# Dogfish3D_-_Driver_Channel.net
KiCad netlist of a schematic drawn in Altium Designer
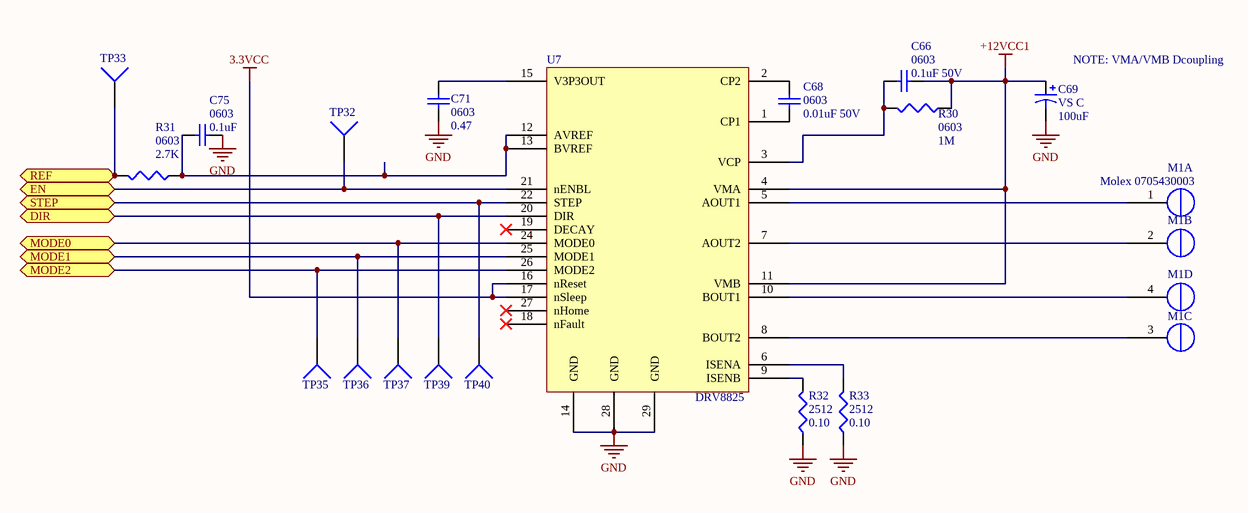
[diagram p0: Dogfish3D - Driver Channel.SchDoc]

(export (version "E")
  (design (tool "Eeschema 10.0.6"))
  (components
    (comp (ref "C66")
      (value "0603")
      (footprint "1608[0603]")
      (description "Capacitor (Semiconductor SIM Model)")
      (fields (field (name "ALTIUM_VALUE") "0.1uF 50V") (field (name "PUBLISHER") "Altium Limited"))
      (libsource (lib "Miscellaneous Devices") (part "Cap Semi"))
    )
    (comp (ref "C68")
      (value "0603")
      (footprint "1608[0603]")
      (description "Capacitor (Semiconductor SIM Model)")
      (fields (field (name "ALTIUM_VALUE") "0.01uF 50V") (field (name "PUBLISHER") "Altium Limited"))
      (libsource (lib "Miscellaneous Devices") (part "Cap Semi"))
    )
    (comp (ref "C69")
      (value "VS C")
      (footprint "Panasonic VS C")
      (description "Polarized Capacitor (Radial)")
      (fields (field (name "ALTIUM_VALUE") "100uF") (field (name "PUBLISHER") "Altium Limited"))
      (libsource (lib "Miscellaneous Devices") (part "Cap Pol1"))
    )
    (comp (ref "C71")
      (value "0603")
      (footprint "1608[0603]")
      (description "Capacitor (Semiconductor SIM Model)")
      (fields (field (name "ALTIUM_VALUE") "0.47") (field (name "PUBLISHER") "Altium Limited"))
      (libsource (lib "Miscellaneous Devices") (part "Cap Semi"))
    )
    (comp (ref "C75")
      (value "0603")
      (footprint "1608[0603]")
      (description "Capacitor (Semiconductor SIM Model)")
      (fields (field (name "ALTIUM_VALUE") "0.1uF") (field (name "PUBLISHER") "Altium Limited"))
      (libsource (lib "Miscellaneous Devices") (part "Cap Semi"))
    )
    (comp (ref "M1")
      (value "Molex 0705430003")
      (footprint "4POL254")
      (description "Molex 4 Pin Clip Connector")
      (libsource (lib "ZMBo Schematic Library") (part "Molex 0705430003 Alt"))
    )
    (comp (ref "R30")
      (value "0603")
      (footprint "J1-0603")
      (description "Resistor")
      (fields (field (name "ALTIUM_VALUE") "1M") (field (name "PUBLISHER") "Altium Limited"))
      (libsource (lib "Miscellaneous Devices") (part "Res3"))
    )
    (comp (ref "R31")
      (value "0603")
      (footprint "J1-0603")
      (description "Resistor")
      (fields (field (name "ALTIUM_VALUE") "2.7K") (field (name "PUBLISHER") "Altium Limited"))
      (libsource (lib "Miscellaneous Devices") (part "Res3"))
    )
    (comp (ref "R32")
      (value "2512")
      (footprint "Resistor2512")
      (description "Resistor")
      (fields (field (name "ALTIUM_VALUE") "0.10") (field (name "PUBLISHER") "Altium Limited"))
      (libsource (lib "Miscellaneous Devices") (part "Res3"))
    )
    (comp (ref "R33")
      (value "2512")
      (footprint "Resistor2512")
      (description "Resistor")
      (fields (field (name "ALTIUM_VALUE") "0.10") (field (name "PUBLISHER") "Altium Limited"))
      (libsource (lib "Miscellaneous Devices") (part "Res3"))
    )
    (comp (ref "TP32")
      (value "TP4")
      (footprint "TP-2")
      (description "Socket")
      (fields (field (name "PUBLISHER") "Altium Limited"))
      (libsource (lib "ZMBo Schematic Library") (part "Socket"))
    )
    (comp (ref "TP33")
      (value "TP4")
      (footprint "TP-2")
      (description "Socket")
      (fields (field (name "PUBLISHER") "Altium Limited"))
      (libsource (lib "ZMBo Schematic Library") (part "Socket"))
    )
    (comp (ref "TP35")
      (value "TP4")
      (footprint "TP-2")
      (description "Socket")
      (fields (field (name "PUBLISHER") "Altium Limited"))
      (libsource (lib "ZMBo Schematic Library") (part "Socket"))
    )
    (comp (ref "TP36")
      (value "TP4")
      (footprint "TP-2")
      (description "Socket")
      (fields (field (name "PUBLISHER") "Altium Limited"))
      (libsource (lib "ZMBo Schematic Library") (part "Socket"))
    )
    (comp (ref "TP37")
      (value "TP4")
      (footprint "TP-2")
      (description "Socket")
      (fields (field (name "PUBLISHER") "Altium Limited"))
      (libsource (lib "ZMBo Schematic Library") (part "Socket"))
    )
    (comp (ref "TP39")
      (value "TP4")
      (footprint "TP-2")
      (description "Socket")
      (fields (field (name "PUBLISHER") "Altium Limited"))
      (libsource (lib "ZMBo Schematic Library") (part "Socket"))
    )
    (comp (ref "TP40")
      (value "TP4")
      (footprint "TP-2")
      (description "Socket")
      (fields (field (name "PUBLISHER") "Altium Limited"))
      (libsource (lib "ZMBo Schematic Library") (part "Socket"))
    )
    (comp (ref "U7")
      (value "DRV8825")
      (footprint "DRV8825")
      (description "DRV8825 Ti Stepper Driver")
      (libsource (lib "ZMBo Schematic Library") (part "DRV8825"))
    )
  )
  (nets
    (net (code "1") (name "+12VCC1") (class "Default")
      (node (ref "C66") (pin "1") (pinfunction "1_1") (pintype "passive"))
      (node (ref "C69") (pin "1") (pinfunction "1_1") (pintype "passive"))
      (node (ref "R30") (pin "1") (pinfunction "1_1") (pintype "passive"))
      (node (ref "U7") (pin "11") (pinfunction "VMB_11") (pintype "passive"))
      (node (ref "U7") (pin "4") (pinfunction "VMA_4") (pintype "passive"))
    )
    (net (code "2") (name "/DIR") (class "Default")
      (node (ref "TP39") (pin "1") (pinfunction "1_1") (pintype "passive"))
      (node (ref "U7") (pin "20") (pinfunction "DIR_20") (pintype "passive"))
    )
    (net (code "3") (name "/EN") (class "Default")
      (node (ref "TP32") (pin "1") (pinfunction "1_1") (pintype "passive"))
      (node (ref "U7") (pin "21") (pinfunction "nENBL_21") (pintype "passive"))
    )
    (net (code "4") (name "/MODE0") (class "Default")
      (node (ref "TP37") (pin "1") (pinfunction "1_1") (pintype "passive"))
      (node (ref "U7") (pin "24") (pinfunction "MODE0_24") (pintype "passive"))
    )
    (net (code "5") (name "/MODE1") (class "Default")
      (node (ref "TP36") (pin "1") (pinfunction "1_1") (pintype "passive"))
      (node (ref "U7") (pin "25") (pinfunction "MODE1_25") (pintype "passive"))
    )
    (net (code "6") (name "/MODE2") (class "Default")
      (node (ref "TP35") (pin "1") (pinfunction "1_1") (pintype "passive"))
      (node (ref "U7") (pin "26") (pinfunction "MODE2_26") (pintype "passive"))
    )
    (net (code "7") (name "/REF") (class "Default")
      (node (ref "R31") (pin "2") (pinfunction "2_2") (pintype "passive"))
      (node (ref "TP33") (pin "1") (pinfunction "1_1") (pintype "passive"))
    )
    (net (code "8") (name "/STEP") (class "Default")
      (node (ref "TP40") (pin "1") (pinfunction "1_1") (pintype "passive"))
      (node (ref "U7") (pin "22") (pinfunction "STEP_22") (pintype "passive"))
    )
    (net (code "9") (name "3.3VCC") (class "Default")
      (node (ref "U7") (pin "16") (pinfunction "nReset_16") (pintype "passive"))
      (node (ref "U7") (pin "17") (pinfunction "nSleep_17") (pintype "passive"))
    )
    (net (code "10") (name "GND") (class "Default")
      (node (ref "C69") (pin "2") (pinfunction "2_2") (pintype "passive"))
      (node (ref "C71") (pin "1") (pinfunction "1_1") (pintype "passive"))
      (node (ref "C75") (pin "1") (pinfunction "1_1") (pintype "passive"))
      (node (ref "R32") (pin "1") (pinfunction "1_1") (pintype "passive"))
      (node (ref "R33") (pin "1") (pinfunction "1_1") (pintype "passive"))
      (node (ref "U7") (pin "14") (pinfunction "GND_14") (pintype "passive"))
      (node (ref "U7") (pin "28") (pinfunction "GND_28") (pintype "passive"))
      (node (ref "U7") (pin "29") (pinfunction "GND_29") (pintype "passive"))
    )
    (net (code "11") (name "Net-(M1A-OUT2B)") (class "Default")
      (node (ref "M1") (pin "1") (pinfunction "OUT2B_1") (pintype "passive"))
      (node (ref "U7") (pin "5") (pinfunction "AOUT1_5") (pintype "passive"))
    )
    (net (code "12") (name "Net-(M1B-OUT2A)") (class "Default")
      (node (ref "M1") (pin "2") (pinfunction "OUT2A_2") (pintype "passive"))
      (node (ref "U7") (pin "7") (pinfunction "AOUT2_7") (pintype "passive"))
    )
    (net (code "13") (name "Net-(M1C-OUT1A)") (class "Default")
      (node (ref "M1") (pin "3") (pinfunction "OUT1A_3") (pintype "passive"))
      (node (ref "U7") (pin "8") (pinfunction "BOUT2_8") (pintype "passive"))
    )
    (net (code "14") (name "Net-(M1D-OUT1B)") (class "Default")
      (node (ref "M1") (pin "4") (pinfunction "OUT1B_4") (pintype "passive"))
      (node (ref "U7") (pin "10") (pinfunction "BOUT1_10") (pintype "passive"))
    )
    (net (code "15") (name "Net-(U7-AVREF)") (class "Default")
      (node (ref "C75") (pin "2") (pinfunction "2_2") (pintype "passive"))
      (node (ref "R31") (pin "1") (pinfunction "1_1") (pintype "passive"))
      (node (ref "U7") (pin "12") (pinfunction "AVREF_12") (pintype "passive"))
      (node (ref "U7") (pin "13") (pinfunction "BVREF_13") (pintype "passive"))
    )
    (net (code "16") (name "Net-(U7-CP1)") (class "Default")
      (node (ref "C68") (pin "1") (pinfunction "1_1") (pintype "passive"))
      (node (ref "U7") (pin "1") (pinfunction "CP1_1") (pintype "passive"))
    )
    (net (code "17") (name "Net-(U7-CP2)") (class "Default")
      (node (ref "C68") (pin "2") (pinfunction "2_2") (pintype "passive"))
      (node (ref "U7") (pin "2") (pinfunction "CP2_2") (pintype "passive"))
    )
    (net (code "18") (name "Net-(U7-ISENA)") (class "Default")
      (node (ref "R33") (pin "2") (pinfunction "2_2") (pintype "passive"))
      (node (ref "U7") (pin "6") (pinfunction "ISENA_6") (pintype "passive"))
    )
    (net (code "19") (name "Net-(U7-ISENB)") (class "Default")
      (node (ref "R32") (pin "2") (pinfunction "2_2") (pintype "passive"))
      (node (ref "U7") (pin "9") (pinfunction "ISENB_9") (pintype "passive"))
    )
    (net (code "20") (name "Net-(U7-V3P3OUT)") (class "Default")
      (node (ref "C71") (pin "2") (pinfunction "2_2") (pintype "passive"))
      (node (ref "U7") (pin "15") (pinfunction "V3P3OUT_15") (pintype "passive"))
    )
    (net (code "21") (name "Net-(U7-VCP)") (class "Default")
      (node (ref "C66") (pin "2") (pinfunction "2_2") (pintype "passive"))
      (node (ref "R30") (pin "2") (pinfunction "2_2") (pintype "passive"))
      (node (ref "U7") (pin "3") (pinfunction "VCP_3") (pintype "passive"))
    )
    (net (code "22") (name "unconnected-(U7-DECAY-Pad19)") (class "Default")
      (node (ref "U7") (pin "19") (pinfunction "DECAY_19") (pintype "passive+no_connect"))
    )
    (net (code "23") (name "unconnected-(U7-NC-Pad23)") (class "Default")
      (node (ref "U7") (pin "23") (pinfunction "NC_23") (pintype "passive"))
    )
    (net (code "24") (name "unconnected-(U7-nFault-Pad18)") (class "Default")
      (node (ref "U7") (pin "18") (pinfunction "nFault_18") (pintype "passive+no_connect"))
    )
    (net (code "25") (name "unconnected-(U7-nHome-Pad27)") (class "Default")
      (node (ref "U7") (pin "27") (pinfunction "nHome_27") (pintype "passive+no_connect"))
    )
  )
)
